# ULN2003A-Relay-Driver.net
KiCad netlist of a schematic drawn in EAGLE
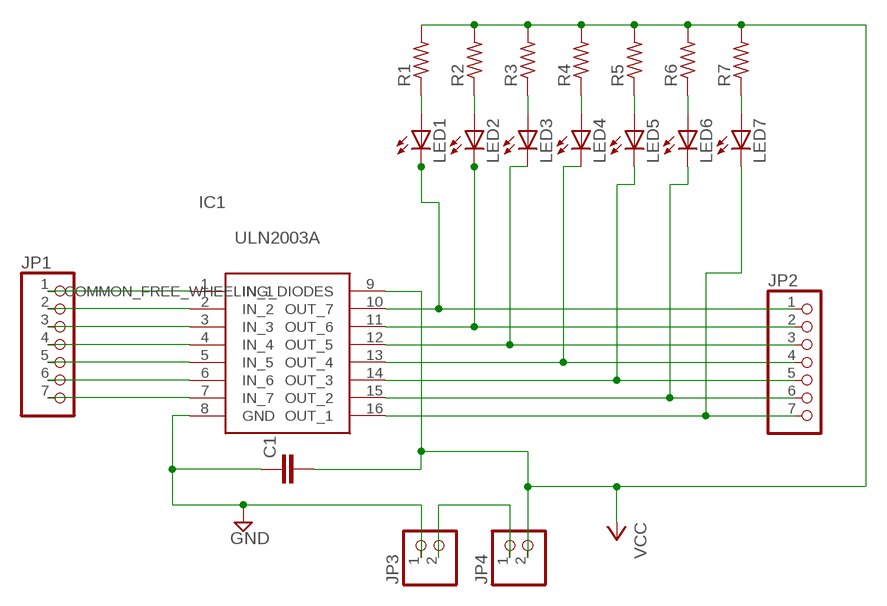
[diagram p0: schematic, sheet 1]

(export (version "E")
  (design (tool "Eeschema 10.0.6"))
  (components
    (comp (ref "C1")
      (value "C5/5")
      (footprint "eagle-import:C5B5")
      (libsource (lib "eagle-import") (part "C5/5"))
    )
    (comp (ref "IC1")
      (value "ULN2003A")
      (footprint "eagle-import:DIP794W56P254L1888H533Q16N")
      (fields (field (name "MOUSER_PART_NUMBER") "511-ULN2003A"))
      (libsource (lib "eagle-import") (part "ULN2003A"))
    )
    (comp (ref "JP1")
      (value "PINHD-1X7")
      (footprint "eagle-import:1X07")
      (libsource (lib "eagle-import") (part "PINHD-1X7"))
    )
    (comp (ref "JP2")
      (value "PINHD-1X7")
      (footprint "eagle-import:1X07")
      (libsource (lib "eagle-import") (part "PINHD-1X7"))
    )
    (comp (ref "JP3")
      (value "PINHD-1X2")
      (footprint "eagle-import:1X02")
      (libsource (lib "eagle-import") (part "PINHD-1X2"))
    )
    (comp (ref "JP4")
      (value "PINHD-1X2")
      (footprint "eagle-import:1X02")
      (libsource (lib "eagle-import") (part "PINHD-1X2"))
    )
    (comp (ref "LED1")
      (value "LED3MM")
      (footprint "eagle-import:LED3MM")
      (libsource (lib "eagle-import") (part "LED3MM"))
    )
    (comp (ref "LED2")
      (value "LED3MM")
      (footprint "eagle-import:LED3MM")
      (libsource (lib "eagle-import") (part "LED3MM"))
    )
    (comp (ref "LED3")
      (value "LED3MM")
      (footprint "eagle-import:LED3MM")
      (libsource (lib "eagle-import") (part "LED3MM"))
    )
    (comp (ref "LED4")
      (value "LED3MM")
      (footprint "eagle-import:LED3MM")
      (libsource (lib "eagle-import") (part "LED3MM"))
    )
    (comp (ref "LED5")
      (value "LED3MM")
      (footprint "eagle-import:LED3MM")
      (libsource (lib "eagle-import") (part "LED3MM"))
    )
    (comp (ref "LED6")
      (value "LED3MM")
      (footprint "eagle-import:LED3MM")
      (libsource (lib "eagle-import") (part "LED3MM"))
    )
    (comp (ref "LED7")
      (value "LED3MM")
      (footprint "eagle-import:LED3MM")
      (libsource (lib "eagle-import") (part "LED3MM"))
    )
    (comp (ref "R1")
      (value "R-US_0204/7")
      (footprint "eagle-import:0204_7")
      (libsource (lib "eagle-import") (part "R-US_0204/7"))
    )
    (comp (ref "R2")
      (value "R-US_0204/7")
      (footprint "eagle-import:0204_7")
      (libsource (lib "eagle-import") (part "R-US_0204/7"))
    )
    (comp (ref "R3")
      (value "R-US_0204/7")
      (footprint "eagle-import:0204_7")
      (libsource (lib "eagle-import") (part "R-US_0204/7"))
    )
    (comp (ref "R4")
      (value "R-US_0204/7")
      (footprint "eagle-import:0204_7")
      (libsource (lib "eagle-import") (part "R-US_0204/7"))
    )
    (comp (ref "R5")
      (value "R-US_0204/7")
      (footprint "eagle-import:0204_7")
      (libsource (lib "eagle-import") (part "R-US_0204/7"))
    )
    (comp (ref "R6")
      (value "R-US_0204/7")
      (footprint "eagle-import:0204_7")
      (libsource (lib "eagle-import") (part "R-US_0204/7"))
    )
    (comp (ref "R7")
      (value "R-US_0204/7")
      (footprint "eagle-import:0204_7")
      (libsource (lib "eagle-import") (part "R-US_0204/7"))
    )
  )
  (nets
    (net (code "1") (name "GND") (class "Default")
      (node (ref "C1") (pin "1") (pinfunction "1_1") (pintype "passive"))
      (node (ref "IC1") (pin "8") (pinfunction "GND_8") (pintype "bidirectional"))
      (node (ref "JP3") (pin "1") (pinfunction "1_1") (pintype "passive"))
    )
    (net (code "2") (name "Net-(IC1-IN_1)") (class "Default")
      (node (ref "IC1") (pin "1") (pinfunction "IN_1_1") (pintype "bidirectional"))
      (node (ref "JP1") (pin "1") (pinfunction "1_1") (pintype "passive"))
    )
    (net (code "3") (name "Net-(IC1-IN_2)") (class "Default")
      (node (ref "IC1") (pin "2") (pinfunction "IN_2_2") (pintype "bidirectional"))
      (node (ref "JP1") (pin "2") (pinfunction "2_2") (pintype "passive"))
    )
    (net (code "4") (name "Net-(IC1-IN_3)") (class "Default")
      (node (ref "IC1") (pin "3") (pinfunction "IN_3_3") (pintype "bidirectional"))
      (node (ref "JP1") (pin "3") (pinfunction "3_3") (pintype "passive"))
    )
    (net (code "5") (name "Net-(IC1-IN_4)") (class "Default")
      (node (ref "IC1") (pin "4") (pinfunction "IN_4_4") (pintype "bidirectional"))
      (node (ref "JP1") (pin "4") (pinfunction "4_4") (pintype "passive"))
    )
    (net (code "6") (name "Net-(IC1-IN_5)") (class "Default")
      (node (ref "IC1") (pin "5") (pinfunction "IN_5_5") (pintype "bidirectional"))
      (node (ref "JP1") (pin "5") (pinfunction "5_5") (pintype "passive"))
    )
    (net (code "7") (name "Net-(IC1-IN_6)") (class "Default")
      (node (ref "IC1") (pin "6") (pinfunction "IN_6_6") (pintype "bidirectional"))
      (node (ref "JP1") (pin "6") (pinfunction "6_6") (pintype "passive"))
    )
    (net (code "8") (name "Net-(IC1-IN_7)") (class "Default")
      (node (ref "IC1") (pin "7") (pinfunction "IN_7_7") (pintype "bidirectional"))
      (node (ref "JP1") (pin "7") (pinfunction "7_7") (pintype "passive"))
    )
    (net (code "9") (name "Net-(IC1-OUT_1)") (class "Default")
      (node (ref "IC1") (pin "16") (pinfunction "OUT_1_16") (pintype "bidirectional"))
      (node (ref "JP2") (pin "7") (pinfunction "7_7") (pintype "passive"))
      (node (ref "LED7") (pin "K") (pinfunction "C_K") (pintype "passive"))
    )
    (net (code "10") (name "Net-(IC1-OUT_2)") (class "Default")
      (node (ref "IC1") (pin "15") (pinfunction "OUT_2_15") (pintype "bidirectional"))
      (node (ref "JP2") (pin "6") (pinfunction "6_6") (pintype "passive"))
      (node (ref "LED6") (pin "K") (pinfunction "C_K") (pintype "passive"))
    )
    (net (code "11") (name "Net-(IC1-OUT_3)") (class "Default")
      (node (ref "IC1") (pin "14") (pinfunction "OUT_3_14") (pintype "bidirectional"))
      (node (ref "JP2") (pin "5") (pinfunction "5_5") (pintype "passive"))
      (node (ref "LED5") (pin "K") (pinfunction "C_K") (pintype "passive"))
    )
    (net (code "12") (name "Net-(IC1-OUT_4)") (class "Default")
      (node (ref "IC1") (pin "13") (pinfunction "OUT_4_13") (pintype "bidirectional"))
      (node (ref "JP2") (pin "4") (pinfunction "4_4") (pintype "passive"))
      (node (ref "LED4") (pin "K") (pinfunction "C_K") (pintype "passive"))
    )
    (net (code "13") (name "Net-(IC1-OUT_5)") (class "Default")
      (node (ref "IC1") (pin "12") (pinfunction "OUT_5_12") (pintype "bidirectional"))
      (node (ref "JP2") (pin "3") (pinfunction "3_3") (pintype "passive"))
      (node (ref "LED3") (pin "K") (pinfunction "C_K") (pintype "passive"))
    )
    (net (code "14") (name "Net-(IC1-OUT_6)") (class "Default")
      (node (ref "IC1") (pin "11") (pinfunction "OUT_6_11") (pintype "bidirectional"))
      (node (ref "JP2") (pin "2") (pinfunction "2_2") (pintype "passive"))
      (node (ref "LED2") (pin "K") (pinfunction "C_K") (pintype "passive"))
    )
    (net (code "15") (name "Net-(IC1-OUT_7)") (class "Default")
      (node (ref "IC1") (pin "10") (pinfunction "OUT_7_10") (pintype "bidirectional"))
      (node (ref "JP2") (pin "1") (pinfunction "1_1") (pintype "passive"))
      (node (ref "LED1") (pin "K") (pinfunction "C_K") (pintype "passive"))
    )
    (net (code "16") (name "Net-(JP3-Pad2)") (class "Default")
      (node (ref "JP3") (pin "2") (pinfunction "2_2") (pintype "passive"))
      (node (ref "JP4") (pin "1") (pinfunction "1_1") (pintype "passive"))
    )
    (net (code "17") (name "Net-(LED1-PadA)") (class "Default")
      (node (ref "LED1") (pin "A") (pinfunction "A_A") (pintype "passive"))
      (node (ref "R1") (pin "1") (pinfunction "1_1") (pintype "passive"))
    )
    (net (code "18") (name "Net-(LED2-PadA)") (class "Default")
      (node (ref "LED2") (pin "A") (pinfunction "A_A") (pintype "passive"))
      (node (ref "R2") (pin "1") (pinfunction "1_1") (pintype "passive"))
    )
    (net (code "19") (name "Net-(LED3-PadA)") (class "Default")
      (node (ref "LED3") (pin "A") (pinfunction "A_A") (pintype "passive"))
      (node (ref "R3") (pin "1") (pinfunction "1_1") (pintype "passive"))
    )
    (net (code "20") (name "Net-(LED4-PadA)") (class "Default")
      (node (ref "LED4") (pin "A") (pinfunction "A_A") (pintype "passive"))
      (node (ref "R4") (pin "1") (pinfunction "1_1") (pintype "passive"))
    )
    (net (code "21") (name "Net-(LED5-PadA)") (class "Default")
      (node (ref "LED5") (pin "A") (pinfunction "A_A") (pintype "passive"))
      (node (ref "R5") (pin "1") (pinfunction "1_1") (pintype "passive"))
    )
    (net (code "22") (name "Net-(LED6-PadA)") (class "Default")
      (node (ref "LED6") (pin "A") (pinfunction "A_A") (pintype "passive"))
      (node (ref "R6") (pin "1") (pinfunction "1_1") (pintype "passive"))
    )
    (net (code "23") (name "Net-(LED7-PadA)") (class "Default")
      (node (ref "LED7") (pin "A") (pinfunction "A_A") (pintype "passive"))
      (node (ref "R7") (pin "1") (pinfunction "1_1") (pintype "passive"))
    )
    (net (code "24") (name "VCC") (class "Default")
      (node (ref "C1") (pin "2") (pinfunction "2_2") (pintype "passive"))
      (node (ref "IC1") (pin "9") (pinfunction "COMMON_FREE_WHEELING_DIODES_9") (pintype "bidirectional"))
      (node (ref "JP4") (pin "2") (pinfunction "2_2") (pintype "passive"))
      (node (ref "R1") (pin "2") (pinfunction "2_2") (pintype "passive"))
      (node (ref "R2") (pin "2") (pinfunction "2_2") (pintype "passive"))
      (node (ref "R3") (pin "2") (pinfunction "2_2") (pintype "passive"))
      (node (ref "R4") (pin "2") (pinfunction "2_2") (pintype "passive"))
      (node (ref "R5") (pin "2") (pinfunction "2_2") (pintype "passive"))
      (node (ref "R6") (pin "2") (pinfunction "2_2") (pintype "passive"))
      (node (ref "R7") (pin "2") (pinfunction "2_2") (pintype "passive"))
    )
  )
)
